# IMU.net
KiCad netlist of a schematic drawn in EAGLE
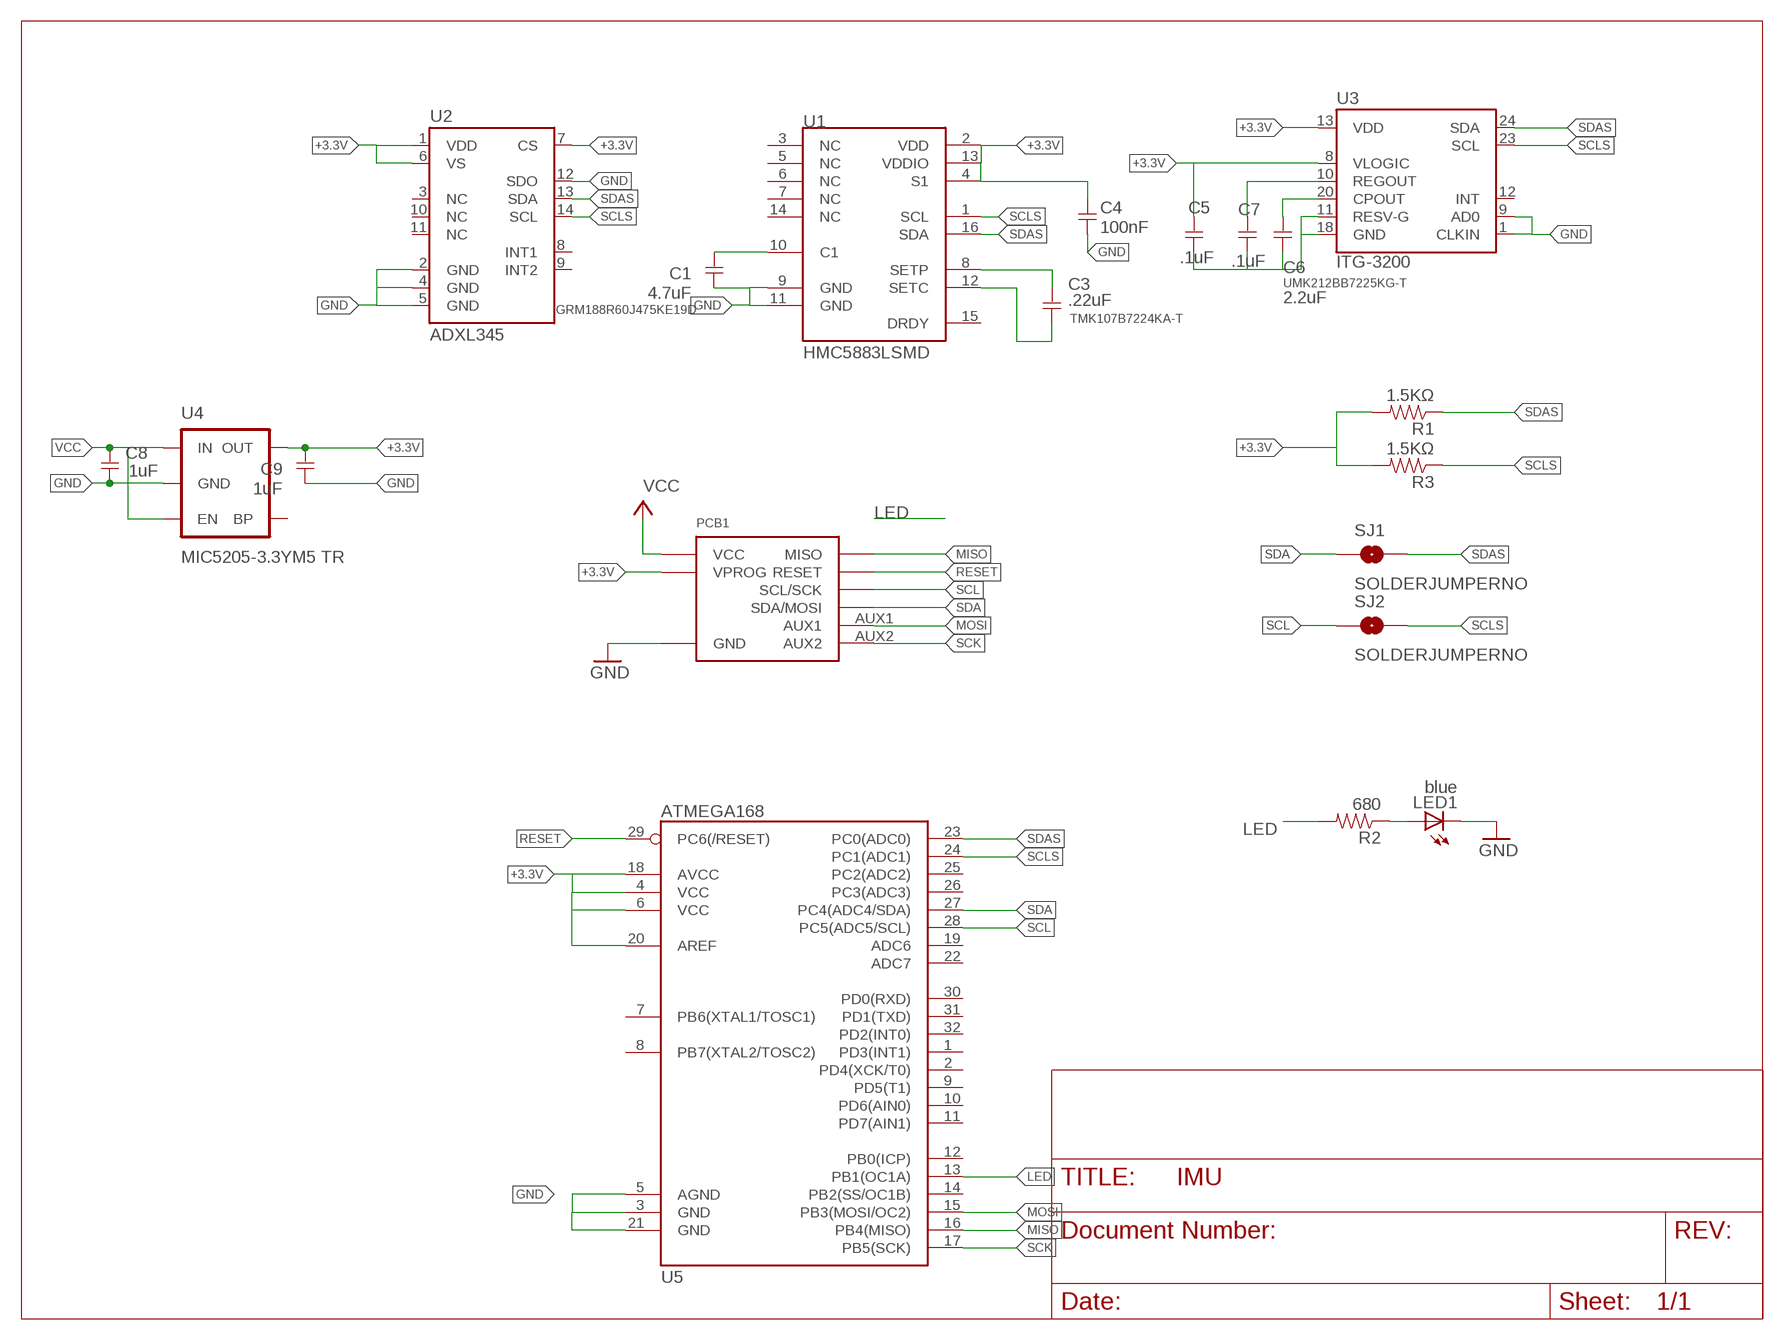
[diagram p0: schematic, sheet 1]

(export (version "E")
  (design (tool "Eeschema 10.0.6"))
  (components
    (comp (ref "C1")
      (value "4.7uF")
      (footprint "eagle-import:0603")
      (fields (field (name "PARTNUM") "C0603C105K4RACTU") (field (name "PARTNUM_1") "GRM188R60J475KE19D"))
      (libsource (lib "eagle-import") (part "CAPACITOR-1UF"))
    )
    (comp (ref "C3")
      (value ".22uF")
      (footprint "eagle-import:0603")
      (fields (field (name "PARTNUM") "C0603C105K4RACTU") (field (name "PARTNUM_1") "TMK107B7224KA-T"))
      (libsource (lib "eagle-import") (part "CAPACITOR-1UF"))
    )
    (comp (ref "C4")
      (value "100nF")
      (footprint "eagle-import:0603")
      (fields (field (name "PARTNUM") "C0603C104K5RACTU"))
      (libsource (lib "eagle-import") (part "CAPACITOR-100NF"))
    )
    (comp (ref "C5")
      (value ".1uF")
      (footprint "eagle-import:0603")
      (fields (field (name "PARTNUM") "C0603C104K5RACTU"))
      (libsource (lib "eagle-import") (part "CAPACITOR-100NF"))
    )
    (comp (ref "C6")
      (value "2.2uF")
      (footprint "eagle-import:0805")
      (fields (field (name "PARTNUM") "UMK212BB7225KG-T"))
      (libsource (lib "eagle-import") (part "CAPACITOR"))
    )
    (comp (ref "C7")
      (value ".1uF")
      (footprint "eagle-import:0603")
      (fields (field (name "PARTNUM") "C0603C104K5RACTU"))
      (libsource (lib "eagle-import") (part "CAPACITOR-100NF"))
    )
    (comp (ref "C8")
      (value "1uF")
      (footprint "eagle-import:0603")
      (fields (field (name "PARTNUM") "C0603C105K4RACTU"))
      (libsource (lib "eagle-import") (part "CAPACITOR-1UF"))
    )
    (comp (ref "C9")
      (value "1uF")
      (footprint "eagle-import:0603")
      (fields (field (name "PARTNUM") "C0603C105K4RACTU"))
      (libsource (lib "eagle-import") (part "CAPACITOR-1UF"))
    )
    (comp (ref "LED1")
      (value "blue")
      (footprint "eagle-import:0805-LED")
      (fields (field (name "PARTNUM") "LTST-C171TBKT"))
      (libsource (lib "eagle-import") (part "LED-0805-BLUE"))
    )
    (comp (ref "PCB1")
      (value "MAGDEVICE-V2")
      (footprint "eagle-import:MAGDEVICE-V2")
      (libsource (lib "eagle-import") (part "MAGDEVICE-V2"))
    )
    (comp (ref "R1")
      (value "1.5KΩ")
      (footprint "eagle-import:0603")
      (fields (field (name "PARTNUM") "ERJ-3EKF1501V"))
      (libsource (lib "eagle-import") (part "RESISTOR-1.5KΩ"))
    )
    (comp (ref "R2")
      (value "680")
      (footprint "eagle-import:0805")
      (libsource (lib "eagle-import") (part "RESISTOR"))
    )
    (comp (ref "R3")
      (value "1.5KΩ")
      (footprint "eagle-import:0603")
      (fields (field (name "PARTNUM") "ERJ-3EKF1501V"))
      (libsource (lib "eagle-import") (part "RESISTOR-1.5KΩ"))
    )
    (comp (ref "SJ1")
      (value "SOLDERJUMPERNO")
      (footprint "eagle-import:SJ_2S-NO")
      (libsource (lib "eagle-import") (part "SOLDERJUMPERNO"))
    )
    (comp (ref "SJ2")
      (value "SOLDERJUMPERNO")
      (footprint "eagle-import:SJ_2S-NO")
      (libsource (lib "eagle-import") (part "SOLDERJUMPERNO"))
    )
    (comp (ref "U1")
      (value "HMC5883LSMD")
      (footprint "eagle-import:16LPCC")
      (libsource (lib "eagle-import") (part "HMC5883LSMD"))
    )
    (comp (ref "U2")
      (value "ADXL345")
      (footprint "eagle-import:LGA14")
      (libsource (lib "eagle-import") (part "ADXL345"))
    )
    (comp (ref "U3")
      (value "ITG-3200")
      (footprint "eagle-import:QFN-24")
      (libsource (lib "eagle-import") (part "ITG-3200"))
    )
    (comp (ref "U4")
      (value "MIC5205-3.3YM5 TR")
      (footprint "eagle-import:SOT23-5")
      (libsource (lib "eagle-import") (part "VREG-MIC5205-3.3V"))
    )
    (comp (ref "U5")
      (value "ATMEGA168")
      (footprint "eagle-import:TQFP32-08")
      (libsource (lib "eagle-import") (part "ATMEGA168"))
    )
  )
  (nets
    (net (code "1") (name "+3.3V") (class "Default")
      (node (ref "C4") (pin "2") (pinfunction "2_2") (pintype "passive"))
      (node (ref "C5") (pin "2") (pinfunction "2_2") (pintype "passive"))
      (node (ref "C9") (pin "2") (pinfunction "2_2") (pintype "passive"))
      (node (ref "PCB1") (pin "VPROG") (pinfunction "VPROG_VPROG") (pintype "bidirectional"))
      (node (ref "R1") (pin "2") (pinfunction "2_2") (pintype "passive"))
      (node (ref "R3") (pin "2") (pinfunction "2_2") (pintype "passive"))
      (node (ref "U1") (pin "13") (pinfunction "VDDIO_13") (pintype "bidirectional"))
      (node (ref "U1") (pin "2") (pinfunction "VDD_2") (pintype "bidirectional"))
      (node (ref "U1") (pin "4") (pinfunction "S1_4") (pintype "bidirectional"))
      (node (ref "U2") (pin "1") (pinfunction "VDD_1") (pintype "bidirectional"))
      (node (ref "U2") (pin "6") (pinfunction "VS_6") (pintype "bidirectional"))
      (node (ref "U2") (pin "7") (pinfunction "CS_7") (pintype "bidirectional"))
      (node (ref "U3") (pin "13") (pinfunction "VDD_13") (pintype "bidirectional"))
      (node (ref "U3") (pin "8") (pinfunction "VLOGIC_8") (pintype "bidirectional"))
      (node (ref "U4") (pin "5") (pinfunction "OUT_5") (pintype "passive"))
      (node (ref "U5") (pin "18") (pinfunction "AVCC_18") (pintype "bidirectional"))
      (node (ref "U5") (pin "20") (pinfunction "AREF_20") (pintype "bidirectional"))
      (node (ref "U5") (pin "4") (pinfunction "VCC_4") (pintype "bidirectional"))
      (node (ref "U5") (pin "6") (pinfunction "VCC_6") (pintype "bidirectional"))
    )
    (net (code "2") (name "GND") (class "Default")
      (node (ref "C1") (pin "1") (pinfunction "1_1") (pintype "passive"))
      (node (ref "C4") (pin "1") (pinfunction "1_1") (pintype "passive"))
      (node (ref "C8") (pin "1") (pinfunction "1_1") (pintype "passive"))
      (node (ref "C9") (pin "1") (pinfunction "1_1") (pintype "passive"))
      (node (ref "LED1") (pin "C") (pinfunction "C_C") (pintype "passive"))
      (node (ref "PCB1") (pin "GND") (pinfunction "GND_GND") (pintype "bidirectional"))
      (node (ref "U1") (pin "11") (pinfunction "GND_11") (pintype "bidirectional"))
      (node (ref "U1") (pin "9") (pinfunction "GND_9") (pintype "bidirectional"))
      (node (ref "U2") (pin "12") (pinfunction "SDO_12") (pintype "bidirectional"))
      (node (ref "U2") (pin "2") (pinfunction "GND_2") (pintype "bidirectional"))
      (node (ref "U2") (pin "4") (pinfunction "GND_4") (pintype "bidirectional"))
      (node (ref "U2") (pin "5") (pinfunction "GND_5") (pintype "bidirectional"))
      (node (ref "U3") (pin "1") (pinfunction "CLKIN_1") (pintype "bidirectional"))
      (node (ref "U3") (pin "9") (pinfunction "AD0_9") (pintype "bidirectional"))
      (node (ref "U4") (pin "2") (pinfunction "GND_2") (pintype "input"))
      (node (ref "U5") (pin "21") (pinfunction "GND_21") (pintype "bidirectional"))
      (node (ref "U5") (pin "3") (pinfunction "GND_3") (pintype "bidirectional"))
      (node (ref "U5") (pin "5") (pinfunction "AGND_5") (pintype "bidirectional"))
    )
    (net (code "3") (name "LED") (class "Default")
      (node (ref "R2") (pin "2") (pinfunction "2_2") (pintype "passive"))
      (node (ref "U5") (pin "13") (pinfunction "PB1(OC1A)_13") (pintype "bidirectional"))
    )
    (net (code "4") (name "MISO") (class "Default")
      (node (ref "PCB1") (pin "MISO") (pinfunction "MISO_MISO") (pintype "bidirectional"))
      (node (ref "U5") (pin "16") (pinfunction "PB4(MISO)_16") (pintype "bidirectional"))
    )
    (net (code "5") (name "MOSI") (class "Default")
      (node (ref "PCB1") (pin "AUX1") (pinfunction "AUX1_AUX1") (pintype "bidirectional"))
      (node (ref "U5") (pin "15") (pinfunction "PB3(MOSI/OC2)_15") (pintype "bidirectional"))
    )
    (net (code "6") (name "Net-(LED1-PadA)") (class "Default")
      (node (ref "LED1") (pin "A") (pinfunction "A_A") (pintype "passive"))
      (node (ref "R2") (pin "1") (pinfunction "1_1") (pintype "passive"))
    )
    (net (code "7") (name "Net-(U1-C1)") (class "Default")
      (node (ref "C1") (pin "2") (pinfunction "2_2") (pintype "passive"))
      (node (ref "U1") (pin "10") (pinfunction "C1_10") (pintype "bidirectional"))
    )
    (net (code "8") (name "Net-(U1-SETC)") (class "Default")
      (node (ref "C3") (pin "1") (pinfunction "1_1") (pintype "passive"))
      (node (ref "U1") (pin "12") (pinfunction "SETC_12") (pintype "bidirectional"))
    )
    (net (code "9") (name "Net-(U1-SETP)") (class "Default")
      (node (ref "C3") (pin "2") (pinfunction "2_2") (pintype "passive"))
      (node (ref "U1") (pin "8") (pinfunction "SETP_8") (pintype "bidirectional"))
    )
    (net (code "10") (name "Net-(U3-CPOUT)") (class "Default")
      (node (ref "C6") (pin "2") (pinfunction "2_2") (pintype "passive"))
      (node (ref "U3") (pin "20") (pinfunction "CPOUT_20") (pintype "bidirectional"))
    )
    (net (code "11") (name "Net-(U3-GND)") (class "Default")
      (node (ref "C5") (pin "1") (pinfunction "1_1") (pintype "passive"))
      (node (ref "C6") (pin "1") (pinfunction "1_1") (pintype "passive"))
      (node (ref "C7") (pin "1") (pinfunction "1_1") (pintype "passive"))
      (node (ref "U3") (pin "11") (pinfunction "RESV-G_11") (pintype "bidirectional"))
      (node (ref "U3") (pin "18") (pinfunction "GND_18") (pintype "bidirectional"))
    )
    (net (code "12") (name "Net-(U3-REGOUT)") (class "Default")
      (node (ref "C7") (pin "2") (pinfunction "2_2") (pintype "passive"))
      (node (ref "U3") (pin "10") (pinfunction "REGOUT_10") (pintype "bidirectional"))
    )
    (net (code "13") (name "RESET") (class "Default")
      (node (ref "PCB1") (pin "RESET") (pinfunction "RESET_RESET") (pintype "bidirectional"))
      (node (ref "U5") (pin "29") (pinfunction "PC6(/RESET)_29") (pintype "bidirectional"))
    )
    (net (code "14") (name "SCK") (class "Default")
      (node (ref "PCB1") (pin "AUX2") (pinfunction "AUX2_AUX2") (pintype "bidirectional"))
      (node (ref "U5") (pin "17") (pinfunction "PB5(SCK)_17") (pintype "bidirectional"))
    )
    (net (code "15") (name "SCL") (class "Default")
      (node (ref "PCB1") (pin "SCL") (pinfunction "SCL/SCK_SCL") (pintype "bidirectional"))
      (node (ref "SJ2") (pin "1") (pinfunction "1_1") (pintype "passive"))
      (node (ref "U5") (pin "28") (pinfunction "PC5(ADC5/SCL)_28") (pintype "bidirectional"))
    )
    (net (code "16") (name "SCLS") (class "Default")
      (node (ref "R3") (pin "1") (pinfunction "1_1") (pintype "passive"))
      (node (ref "SJ2") (pin "2") (pinfunction "2_2") (pintype "passive"))
      (node (ref "U1") (pin "1") (pinfunction "SCL_1") (pintype "bidirectional"))
      (node (ref "U2") (pin "14") (pinfunction "SCL_14") (pintype "bidirectional"))
      (node (ref "U3") (pin "23") (pinfunction "SCL_23") (pintype "bidirectional"))
      (node (ref "U5") (pin "24") (pinfunction "PC1(ADC1)_24") (pintype "bidirectional"))
    )
    (net (code "17") (name "SDA") (class "Default")
      (node (ref "PCB1") (pin "SDA") (pinfunction "SDA/MOSI_SDA") (pintype "bidirectional"))
      (node (ref "SJ1") (pin "1") (pinfunction "1_1") (pintype "passive"))
      (node (ref "U5") (pin "27") (pinfunction "PC4(ADC4/SDA)_27") (pintype "bidirectional"))
    )
    (net (code "18") (name "SDAS") (class "Default")
      (node (ref "R1") (pin "1") (pinfunction "1_1") (pintype "passive"))
      (node (ref "SJ1") (pin "2") (pinfunction "2_2") (pintype "passive"))
      (node (ref "U1") (pin "16") (pinfunction "SDA_16") (pintype "bidirectional"))
      (node (ref "U2") (pin "13") (pinfunction "SDA_13") (pintype "bidirectional"))
      (node (ref "U3") (pin "24") (pinfunction "SDA_24") (pintype "bidirectional"))
      (node (ref "U5") (pin "23") (pinfunction "PC0(ADC0)_23") (pintype "bidirectional"))
    )
    (net (code "19") (name "VCC") (class "Default")
      (node (ref "C8") (pin "2") (pinfunction "2_2") (pintype "passive"))
      (node (ref "PCB1") (pin "VCC") (pinfunction "VCC_VCC") (pintype "bidirectional"))
      (node (ref "U4") (pin "1") (pinfunction "IN_1") (pintype "input"))
      (node (ref "U4") (pin "3") (pinfunction "EN_3") (pintype "input"))
    )
    (net (code "20") (name "unconnected-(U1-DRDY-Pad15)") (class "Default")
      (node (ref "U1") (pin "15") (pinfunction "DRDY_15") (pintype "bidirectional"))
    )
    (net (code "21") (name "unconnected-(U1-NC-Pad3)") (class "Default")
      (node (ref "U1") (pin "3") (pinfunction "NC_3") (pintype "bidirectional"))
    )
    (net (code "22") (name "unconnected-(U1-NC-Pad5)") (class "Default")
      (node (ref "U1") (pin "5") (pinfunction "NC_5") (pintype "bidirectional"))
    )
    (net (code "23") (name "unconnected-(U1-NC-Pad6)") (class "Default")
      (node (ref "U1") (pin "6") (pinfunction "NC_6") (pintype "bidirectional"))
    )
    (net (code "24") (name "unconnected-(U1-NC-Pad7)") (class "Default")
      (node (ref "U1") (pin "7") (pinfunction "NC_7") (pintype "bidirectional"))
    )
    (net (code "25") (name "unconnected-(U1-NC-Pad14)") (class "Default")
      (node (ref "U1") (pin "14") (pinfunction "NC_14") (pintype "bidirectional"))
    )
    (net (code "26") (name "unconnected-(U2-INT1-Pad8)") (class "Default")
      (node (ref "U2") (pin "8") (pinfunction "INT1_8") (pintype "bidirectional"))
    )
    (net (code "27") (name "unconnected-(U2-INT2-Pad9)") (class "Default")
      (node (ref "U2") (pin "9") (pinfunction "INT2_9") (pintype "bidirectional"))
    )
    (net (code "28") (name "unconnected-(U2-NC-Pad3)") (class "Default")
      (node (ref "U2") (pin "3") (pinfunction "NC_3") (pintype "bidirectional"))
    )
    (net (code "29") (name "unconnected-(U2-NC-Pad10)") (class "Default")
      (node (ref "U2") (pin "10") (pinfunction "NC_10") (pintype "bidirectional"))
    )
    (net (code "30") (name "unconnected-(U2-NC-Pad11)") (class "Default")
      (node (ref "U2") (pin "11") (pinfunction "NC_11") (pintype "bidirectional"))
    )
    (net (code "31") (name "unconnected-(U3-INT-Pad12)") (class "Default")
      (node (ref "U3") (pin "12") (pinfunction "INT_12") (pintype "bidirectional"))
    )
    (net (code "32") (name "unconnected-(U4-BP-Pad4)") (class "Default")
      (node (ref "U4") (pin "4") (pinfunction "BP_4") (pintype "input"))
    )
    (net (code "33") (name "unconnected-(U5-ADC6-Pad19)") (class "Default")
      (node (ref "U5") (pin "19") (pinfunction "ADC6_19") (pintype "bidirectional"))
    )
    (net (code "34") (name "unconnected-(U5-ADC7-Pad22)") (class "Default")
      (node (ref "U5") (pin "22") (pinfunction "ADC7_22") (pintype "bidirectional"))
    )
    (net (code "35") (name "unconnected-(U5-PB0(ICP)-Pad12)") (class "Default")
      (node (ref "U5") (pin "12") (pinfunction "PB0(ICP)_12") (pintype "bidirectional"))
    )
    (net (code "36") (name "unconnected-(U5-PB2(SS{slash}OC1B)-Pad14)") (class "Default")
      (node (ref "U5") (pin "14") (pinfunction "PB2(SS/OC1B)_14") (pintype "bidirectional"))
    )
    (net (code "37") (name "unconnected-(U5-PB6(XTAL1{slash}TOSC1)-Pad7)") (class "Default")
      (node (ref "U5") (pin "7") (pinfunction "PB6(XTAL1/TOSC1)_7") (pintype "bidirectional"))
    )
    (net (code "38") (name "unconnected-(U5-PB7(XTAL2{slash}TOSC2)-Pad8)") (class "Default")
      (node (ref "U5") (pin "8") (pinfunction "PB7(XTAL2/TOSC2)_8") (pintype "bidirectional"))
    )
    (net (code "39") (name "unconnected-(U5-PC2(ADC2)-Pad25)") (class "Default")
      (node (ref "U5") (pin "25") (pinfunction "PC2(ADC2)_25") (pintype "bidirectional"))
    )
    (net (code "40") (name "unconnected-(U5-PC3(ADC3)-Pad26)") (class "Default")
      (node (ref "U5") (pin "26") (pinfunction "PC3(ADC3)_26") (pintype "bidirectional"))
    )
    (net (code "41") (name "unconnected-(U5-PD0(RXD)-Pad30)") (class "Default")
      (node (ref "U5") (pin "30") (pinfunction "PD0(RXD)_30") (pintype "bidirectional"))
    )
    (net (code "42") (name "unconnected-(U5-PD1(TXD)-Pad31)") (class "Default")
      (node (ref "U5") (pin "31") (pinfunction "PD1(TXD)_31") (pintype "bidirectional"))
    )
    (net (code "43") (name "unconnected-(U5-PD2(INT0)-Pad32)") (class "Default")
      (node (ref "U5") (pin "32") (pinfunction "PD2(INT0)_32") (pintype "bidirectional"))
    )
    (net (code "44") (name "unconnected-(U5-PD3(INT1)-Pad1)") (class "Default")
      (node (ref "U5") (pin "1") (pinfunction "PD3(INT1)_1") (pintype "bidirectional"))
    )
    (net (code "45") (name "unconnected-(U5-PD4(XCK{slash}T0)-Pad2)") (class "Default")
      (node (ref "U5") (pin "2") (pinfunction "PD4(XCK/T0)_2") (pintype "bidirectional"))
    )
    (net (code "46") (name "unconnected-(U5-PD5(T1)-Pad9)") (class "Default")
      (node (ref "U5") (pin "9") (pinfunction "PD5(T1)_9") (pintype "bidirectional"))
    )
    (net (code "47") (name "unconnected-(U5-PD6(AIN0)-Pad10)") (class "Default")
      (node (ref "U5") (pin "10") (pinfunction "PD6(AIN0)_10") (pintype "bidirectional"))
    )
    (net (code "48") (name "unconnected-(U5-PD7(AIN1)-Pad11)") (class "Default")
      (node (ref "U5") (pin "11") (pinfunction "PD7(AIN1)_11") (pintype "bidirectional"))
    )
  )
)
